# ch340_usb.net
KiCad netlist of a schematic drawn in EAGLE
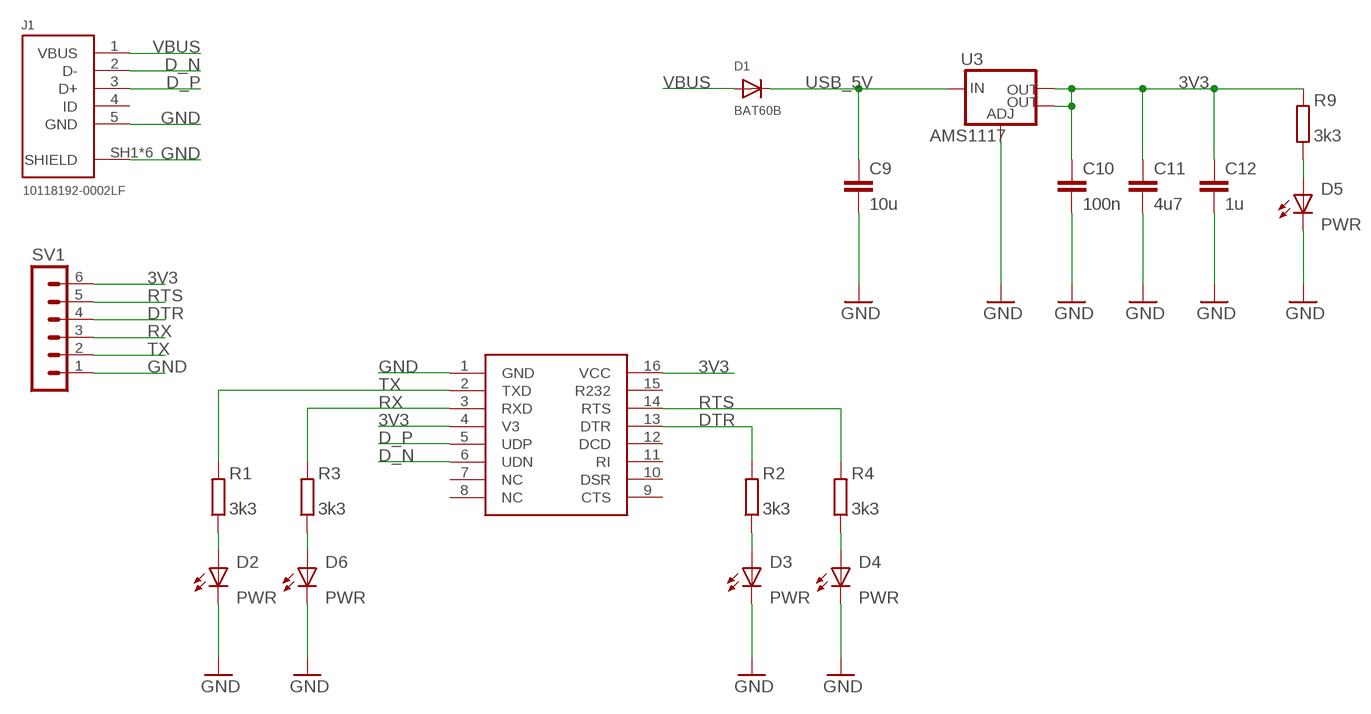
[diagram p0: schematic, sheet 1]

(export (version "E")
  (design (tool "Eeschema 10.0.6"))
  (components
    (comp (ref "C9")
      (value "10u")
      (footprint "eagle-import:C0603")
      (libsource (lib "eagle-import") (part "C-EUC0603"))
    )
    (comp (ref "C10")
      (value "100n")
      (footprint "eagle-import:C0603")
      (libsource (lib "eagle-import") (part "C-EUC0603"))
    )
    (comp (ref "C11")
      (value "4u7")
      (footprint "eagle-import:C0603")
      (libsource (lib "eagle-import") (part "C-EUC0603"))
    )
    (comp (ref "C12")
      (value "1u")
      (footprint "eagle-import:C0603")
      (libsource (lib "eagle-import") (part "C-EUC0603"))
    )
    (comp (ref "D1")
      (value "BAT60B")
      (footprint "eagle-import:SOD-323F")
      (libsource (lib "eagle-import") (part "DIODESOD-323F"))
    )
    (comp (ref "D2")
      (value "PWR")
      (footprint "eagle-import:CHIPLED_0805")
      (libsource (lib "eagle-import") (part "LEDCHIPLED_0805"))
    )
    (comp (ref "D3")
      (value "PWR")
      (footprint "eagle-import:CHIPLED_0805")
      (libsource (lib "eagle-import") (part "LEDCHIPLED_0805"))
    )
    (comp (ref "D4")
      (value "PWR")
      (footprint "eagle-import:CHIPLED_0805")
      (libsource (lib "eagle-import") (part "LEDCHIPLED_0805"))
    )
    (comp (ref "D5")
      (value "PWR")
      (footprint "eagle-import:CHIPLED_0805")
      (libsource (lib "eagle-import") (part "LEDCHIPLED_0805"))
    )
    (comp (ref "D6")
      (value "PWR")
      (footprint "eagle-import:CHIPLED_0805")
      (libsource (lib "eagle-import") (part "LEDCHIPLED_0805"))
    )
    (comp (ref "J1")
      (value "10118192-0002LF")
      (footprint "eagle-import:10118192-0002LF")
      (fields
        (field (name "DIGIKEY_PARTNO") "609-5379-2-ND")
        (field (name "MANUFACTURER") "Amphenol ICC (FCI)")
        (field (name "CREATED_BY") "PCBLayout.com")
      )
      (libsource (lib "eagle-import") (part "10118192-0002LF"))
    )
    (comp (ref "R1")
      (value "3k3")
      (footprint "eagle-import:R0603")
      (libsource (lib "eagle-import") (part "R-EU_R0603"))
    )
    (comp (ref "R2")
      (value "3k3")
      (footprint "eagle-import:R0603")
      (libsource (lib "eagle-import") (part "R-EU_R0603"))
    )
    (comp (ref "R3")
      (value "3k3")
      (footprint "eagle-import:R0603")
      (libsource (lib "eagle-import") (part "R-EU_R0603"))
    )
    (comp (ref "R4")
      (value "3k3")
      (footprint "eagle-import:R0603")
      (libsource (lib "eagle-import") (part "R-EU_R0603"))
    )
    (comp (ref "R9")
      (value "3k3")
      (footprint "eagle-import:R0603")
      (libsource (lib "eagle-import") (part "R-EU_R0603"))
    )
    (comp (ref "SV1")
      (value "MA06-1")
      (footprint "eagle-import:MA06-1")
      (libsource (lib "eagle-import") (part "MA06-1"))
    )
    (comp (ref "U$1")
      (value "CH340")
      (footprint "eagle-import:SOP16")
      (libsource (lib "eagle-import") (part "CH340"))
    )
    (comp (ref "U3")
      (value "AMS1117")
      (footprint "eagle-import:SOT223")
      (libsource (lib "eagle-import") (part "V_REG_LM1117SOT223"))
    )
  )
  (nets
    (net (code "1") (name "/3V3") (class "Default")
      (node (ref "C10") (pin "1") (pinfunction "1_1") (pintype "passive"))
      (node (ref "C11") (pin "1") (pinfunction "1_1") (pintype "passive"))
      (node (ref "C12") (pin "1") (pinfunction "1_1") (pintype "passive"))
      (node (ref "R9") (pin "2") (pinfunction "2_2") (pintype "passive"))
      (node (ref "SV1") (pin "6") (pinfunction "6_6") (pintype "passive"))
      (node (ref "U$1") (pin "16") (pinfunction "VCC_16") (pintype "bidirectional"))
      (node (ref "U$1") (pin "4") (pinfunction "V3_4") (pintype "bidirectional"))
      (node (ref "U3") (pin "2") (pinfunction "OUT_2") (pintype "output"))
      (node (ref "U3") (pin "4") (pinfunction "OUT_4") (pintype "output"))
    )
    (net (code "2") (name "/DTR") (class "Default")
      (node (ref "R2") (pin "2") (pinfunction "2_2") (pintype "passive"))
      (node (ref "SV1") (pin "4") (pinfunction "4_4") (pintype "passive"))
      (node (ref "U$1") (pin "13") (pinfunction "DTR_13") (pintype "bidirectional"))
    )
    (net (code "3") (name "/D_N") (class "Default")
      (node (ref "J1") (pin "2") (pinfunction "D-_2") (pintype "passive"))
      (node (ref "U$1") (pin "6") (pinfunction "UDN_6") (pintype "bidirectional"))
    )
    (net (code "4") (name "/D_P") (class "Default")
      (node (ref "J1") (pin "3") (pinfunction "D+_3") (pintype "passive"))
      (node (ref "U$1") (pin "5") (pinfunction "UDP_5") (pintype "bidirectional"))
    )
    (net (code "5") (name "/RTS") (class "Default")
      (node (ref "R4") (pin "2") (pinfunction "2_2") (pintype "passive"))
      (node (ref "SV1") (pin "5") (pinfunction "5_5") (pintype "passive"))
      (node (ref "U$1") (pin "14") (pinfunction "RTS_14") (pintype "bidirectional"))
    )
    (net (code "6") (name "/RX") (class "Default")
      (node (ref "R3") (pin "2") (pinfunction "2_2") (pintype "passive"))
      (node (ref "SV1") (pin "3") (pinfunction "3_3") (pintype "passive"))
      (node (ref "U$1") (pin "3") (pinfunction "RXD_3") (pintype "bidirectional"))
    )
    (net (code "7") (name "/TX") (class "Default")
      (node (ref "R1") (pin "2") (pinfunction "2_2") (pintype "passive"))
      (node (ref "SV1") (pin "2") (pinfunction "2_2") (pintype "passive"))
      (node (ref "U$1") (pin "2") (pinfunction "TXD_2") (pintype "bidirectional"))
    )
    (net (code "8") (name "/USB_5V") (class "Default")
      (node (ref "C9") (pin "1") (pinfunction "1_1") (pintype "passive"))
      (node (ref "D1") (pin "C") (pinfunction "C_C") (pintype "passive"))
      (node (ref "U3") (pin "3") (pinfunction "IN_3") (pintype "input"))
    )
    (net (code "9") (name "/VBUS") (class "Default")
      (node (ref "D1") (pin "A") (pinfunction "A_A") (pintype "passive"))
      (node (ref "J1") (pin "1") (pinfunction "VBUS_1") (pintype "passive"))
    )
    (net (code "10") (name "GND") (class "Default")
      (node (ref "C10") (pin "2") (pinfunction "2_2") (pintype "passive"))
      (node (ref "C11") (pin "2") (pinfunction "2_2") (pintype "passive"))
      (node (ref "C12") (pin "2") (pinfunction "2_2") (pintype "passive"))
      (node (ref "C9") (pin "2") (pinfunction "2_2") (pintype "passive"))
      (node (ref "D2") (pin "C") (pinfunction "C_C") (pintype "passive"))
      (node (ref "D3") (pin "C") (pinfunction "C_C") (pintype "passive"))
      (node (ref "D4") (pin "C") (pinfunction "C_C") (pintype "passive"))
      (node (ref "D5") (pin "C") (pinfunction "C_C") (pintype "passive"))
      (node (ref "D6") (pin "C") (pinfunction "C_C") (pintype "passive"))
      (node (ref "J1") (pin "5") (pinfunction "GND_5") (pintype "passive"))
      (node (ref "J1") (pin "SH1") (pinfunction "SHIELD_SH1") (pintype "power_in"))
      (node (ref "J1") (pin "SH2") (pinfunction "SHIELD_SH2") (pintype "power_in"))
      (node (ref "J1") (pin "SH3") (pinfunction "SHIELD_SH3") (pintype "power_in"))
      (node (ref "J1") (pin "SH4") (pinfunction "SHIELD_SH4") (pintype "power_in"))
      (node (ref "J1") (pin "SH5") (pinfunction "SHIELD_SH5") (pintype "power_in"))
      (node (ref "J1") (pin "SH6") (pinfunction "SHIELD_SH6") (pintype "power_in"))
      (node (ref "SV1") (pin "1") (pinfunction "1_1") (pintype "passive"))
      (node (ref "U$1") (pin "1") (pinfunction "GND_1") (pintype "bidirectional"))
      (node (ref "U3") (pin "1") (pinfunction "ADJ_1") (pintype "input"))
    )
    (net (code "11") (name "Net-(D2-PadA)") (class "Default")
      (node (ref "D2") (pin "A") (pinfunction "A_A") (pintype "passive"))
      (node (ref "R1") (pin "1") (pinfunction "1_1") (pintype "passive"))
    )
    (net (code "12") (name "Net-(D3-PadA)") (class "Default")
      (node (ref "D3") (pin "A") (pinfunction "A_A") (pintype "passive"))
      (node (ref "R2") (pin "1") (pinfunction "1_1") (pintype "passive"))
    )
    (net (code "13") (name "Net-(D4-PadA)") (class "Default")
      (node (ref "D4") (pin "A") (pinfunction "A_A") (pintype "passive"))
      (node (ref "R4") (pin "1") (pinfunction "1_1") (pintype "passive"))
    )
    (net (code "14") (name "Net-(D5-PadA)") (class "Default")
      (node (ref "D5") (pin "A") (pinfunction "A_A") (pintype "passive"))
      (node (ref "R9") (pin "1") (pinfunction "1_1") (pintype "passive"))
    )
    (net (code "15") (name "Net-(D6-PadA)") (class "Default")
      (node (ref "D6") (pin "A") (pinfunction "A_A") (pintype "passive"))
      (node (ref "R3") (pin "1") (pinfunction "1_1") (pintype "passive"))
    )
    (net (code "16") (name "unconnected-(J1-ID-Pad4)") (class "Default")
      (node (ref "J1") (pin "4") (pinfunction "ID_4") (pintype "passive"))
    )
    (net (code "17") (name "unconnected-(U$1-CTS-Pad9)") (class "Default")
      (node (ref "U$1") (pin "9") (pinfunction "CTS_9") (pintype "bidirectional"))
    )
    (net (code "18") (name "unconnected-(U$1-DCD-Pad12)") (class "Default")
      (node (ref "U$1") (pin "12") (pinfunction "DCD_12") (pintype "bidirectional"))
    )
    (net (code "19") (name "unconnected-(U$1-DSR-Pad10)") (class "Default")
      (node (ref "U$1") (pin "10") (pinfunction "DSR_10") (pintype "bidirectional"))
    )
    (net (code "20") (name "unconnected-(U$1-NC-Pad7)") (class "Default")
      (node (ref "U$1") (pin "7") (pinfunction "NC_7") (pintype "bidirectional"))
    )
    (net (code "21") (name "unconnected-(U$1-NC-Pad8)") (class "Default")
      (node (ref "U$1") (pin "8") (pinfunction "NC_8") (pintype "bidirectional"))
    )
    (net (code "22") (name "unconnected-(U$1-R232-Pad15)") (class "Default")
      (node (ref "U$1") (pin "15") (pinfunction "R232_15") (pintype "bidirectional"))
    )
    (net (code "23") (name "unconnected-(U$1-RI-Pad11)") (class "Default")
      (node (ref "U$1") (pin "11") (pinfunction "RI_11") (pintype "bidirectional"))
    )
  )
)
